# Trailer_Wireup.net
KiCad netlist of a schematic drawn in EAGLE
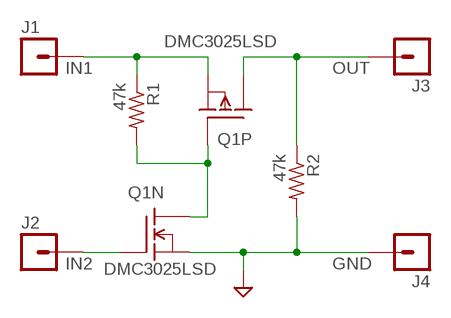
[diagram p0: schematic, sheet 1]

(export (version "E")
  (design (tool "Eeschema 10.0.6"))
  (components
    (comp (ref "J1")
      (value "CONN-1-SCREW-#6-0.3IN")
      (footprint "eagle-import:SCREW_TERMINAL-#6-0.3IN")
      (libsource (lib "eagle-import") (part "CONN-1-SCREW-#6-0.3IN"))
    )
    (comp (ref "J2")
      (value "CONN-1-SCREW-#6-0.3IN")
      (footprint "eagle-import:SCREW_TERMINAL-#6-0.3IN")
      (libsource (lib "eagle-import") (part "CONN-1-SCREW-#6-0.3IN"))
    )
    (comp (ref "J3")
      (value "CONN-1-SCREW-#6-0.3IN")
      (footprint "eagle-import:SCREW_TERMINAL-#6-0.3IN")
      (libsource (lib "eagle-import") (part "CONN-1-SCREW-#6-0.3IN"))
    )
    (comp (ref "J4")
      (value "CONN-1-SCREW-#6-0.3IN")
      (footprint "eagle-import:SCREW_TERMINAL-#6-0.3IN")
      (libsource (lib "eagle-import") (part "CONN-1-SCREW-#6-0.3IN"))
    )
    (comp (ref "Q1")
      (value "DMC3025LSD")
      (footprint "eagle-import:SO8")
      (libsource (lib "eagle-import") (part "DMC3025LSD"))
    )
    (comp (ref "R1")
      (value "47k")
      (footprint "eagle-import:0603")
      (libsource (lib "eagle-import") (part "R-US0603"))
    )
    (comp (ref "R2")
      (value "47k")
      (footprint "eagle-import:0603")
      (libsource (lib "eagle-import") (part "R-US0603"))
    )
  )
  (nets
    (net (code "1") (name "/IN1") (class "Default")
      (node (ref "J1") (pin "1") (pinfunction "1_1") (pintype "passive"))
      (node (ref "Q1") (pin "3") (pinfunction "S_3") (pintype "passive"))
      (node (ref "R1") (pin "1") (pinfunction "1_1") (pintype "passive"))
    )
    (net (code "2") (name "/IN2") (class "Default")
      (node (ref "J2") (pin "1") (pinfunction "1_1") (pintype "passive"))
      (node (ref "Q1") (pin "2") (pinfunction "G_2") (pintype "passive"))
    )
    (net (code "3") (name "/OUT") (class "Default")
      (node (ref "J3") (pin "1") (pinfunction "1_1") (pintype "passive"))
      (node (ref "Q1") (pin "5") (pinfunction "D_5") (pintype "passive"))
      (node (ref "Q1") (pin "6") (pinfunction "D_6") (pintype "passive"))
      (node (ref "R2") (pin "1") (pinfunction "1_1") (pintype "passive"))
    )
    (net (code "4") (name "GND") (class "Default")
      (node (ref "J4") (pin "1") (pinfunction "1_1") (pintype "passive"))
      (node (ref "Q1") (pin "1") (pinfunction "S_1") (pintype "passive"))
      (node (ref "R2") (pin "2") (pinfunction "2_2") (pintype "passive"))
    )
    (net (code "5") (name "Net-(Q1B-G)") (class "Default")
      (node (ref "Q1") (pin "4") (pinfunction "G_4") (pintype "passive"))
      (node (ref "Q1") (pin "7") (pinfunction "D_7") (pintype "passive"))
      (node (ref "Q1") (pin "8") (pinfunction "D_8") (pintype "passive"))
      (node (ref "R1") (pin "2") (pinfunction "2_2") (pintype "passive"))
    )
  )
)
